# contactless-thermometer.net
KiCad netlist of a schematic drawn in EAGLE
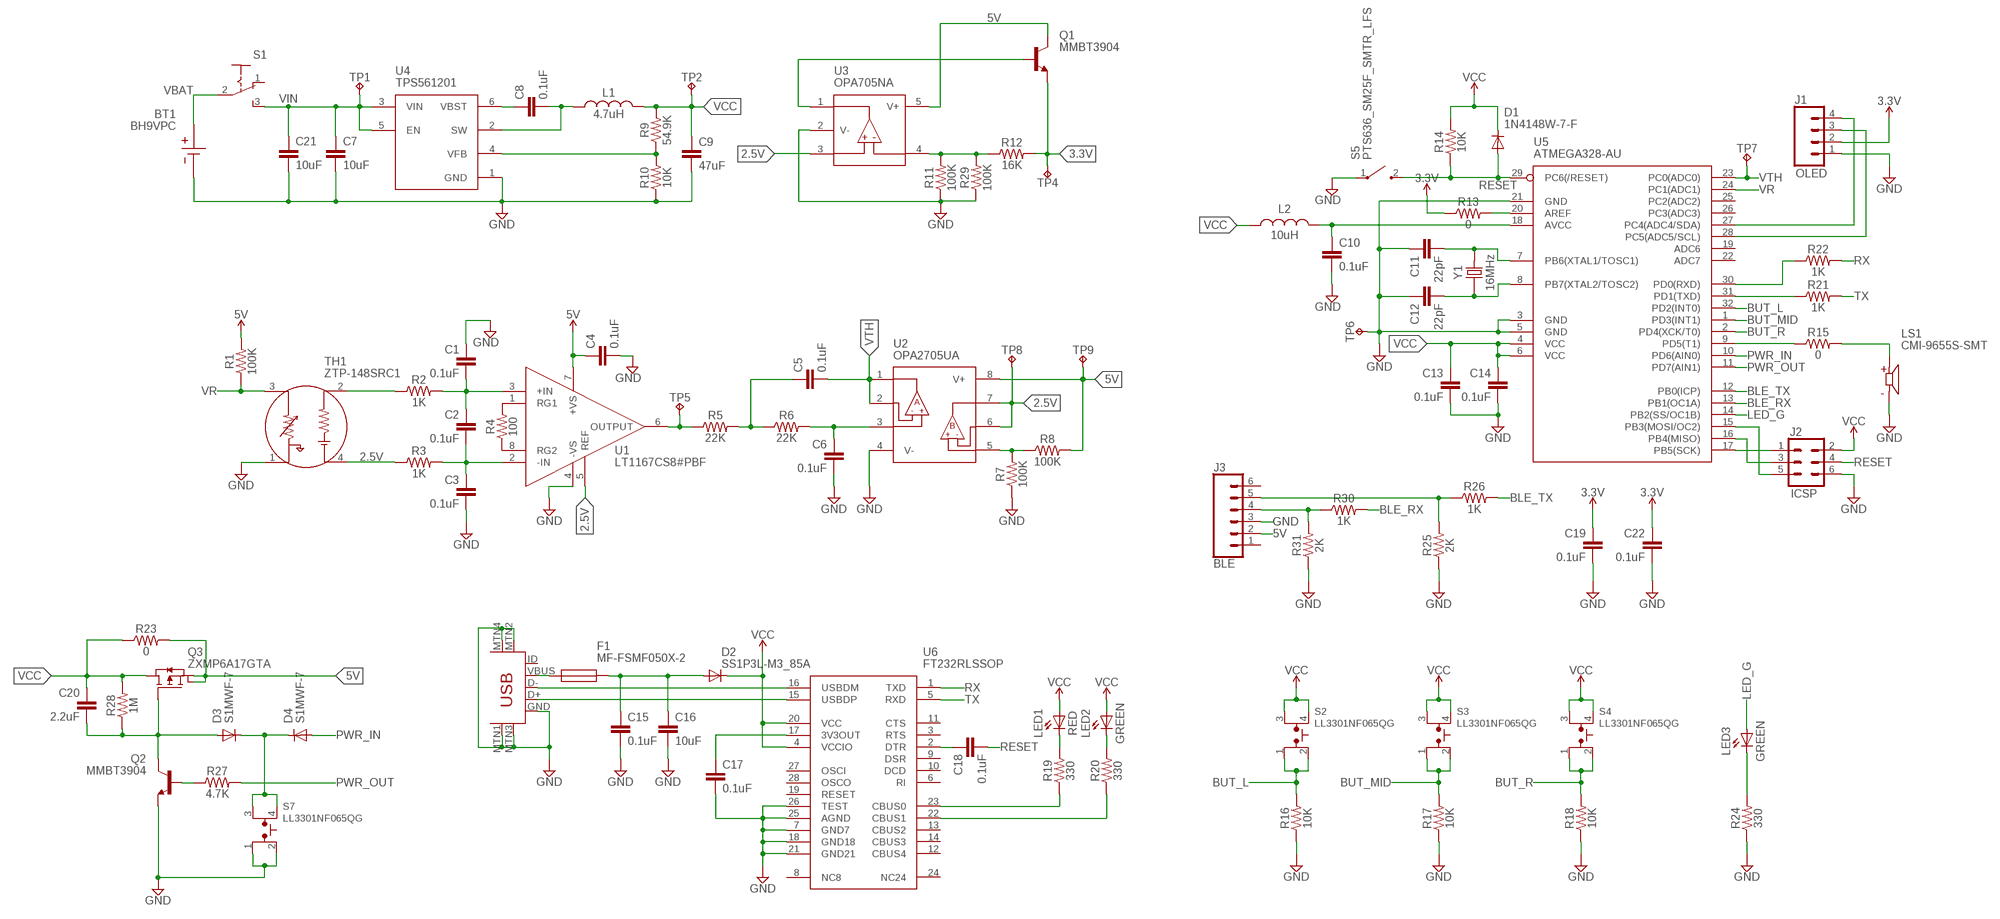
[diagram p0: schematic, sheet 1]

(export (version "E")
  (design (tool "Eeschema 10.0.6"))
  (components
    (comp (ref "BT1")
      (value "BH9VPC")
      (footprint "eagle-import:BAT_BH9VPC")
      (fields (field (name "DIGI-KEY_PART_NUMBER") "BH9V-PC-ND") (field (name "MF") "MPD"))
      (libsource (lib "eagle-import") (part "BH9VPC"))
    )
    (comp (ref "C1")
      (value "0.1uF")
      (footprint "eagle-import:0603")
      (libsource (lib "eagle-import") (part "0.1UF-0603-25V-(+80/-20%)"))
    )
    (comp (ref "C2")
      (value "0.1uF")
      (footprint "eagle-import:0603")
      (libsource (lib "eagle-import") (part "0.1UF-0603-25V-(+80/-20%)"))
    )
    (comp (ref "C3")
      (value "0.1uF")
      (footprint "eagle-import:0603")
      (libsource (lib "eagle-import") (part "0.1UF-0603-25V-(+80/-20%)"))
    )
    (comp (ref "C4")
      (value "0.1uF")
      (footprint "eagle-import:0603")
      (libsource (lib "eagle-import") (part "0.1UF-0603-25V-(+80/-20%)"))
    )
    (comp (ref "C5")
      (value "0.1uF")
      (footprint "eagle-import:0603")
      (libsource (lib "eagle-import") (part "0.1UF-0603-25V-(+80/-20%)"))
    )
    (comp (ref "C6")
      (value "0.1uF")
      (footprint "eagle-import:0603")
      (libsource (lib "eagle-import") (part "0.1UF-0603-25V-(+80/-20%)"))
    )
    (comp (ref "C7")
      (value "10uF")
      (footprint "eagle-import:CAPC2012X145N")
      (fields (field (name "MF") "Murata") (field (name "MP") "GRM21BR6YA106KE43L"))
      (libsource (lib "eagle-import") (part "GRM21BR6YA106KE43L"))
    )
    (comp (ref "C8")
      (value "0.1uF")
      (footprint "eagle-import:0603")
      (libsource (lib "eagle-import") (part "0.1UF-0603-25V-(+80/-20%)"))
    )
    (comp (ref "C9")
      (value "47uF")
      (footprint "eagle-import:1206")
      (libsource (lib "eagle-import") (part "10UF-1206-6.3V-20%"))
    )
    (comp (ref "C10")
      (value "0.1uF")
      (footprint "eagle-import:0603")
      (libsource (lib "eagle-import") (part "0.1UF-0603-25V-(+80/-20%)"))
    )
    (comp (ref "C11")
      (value "22pF")
      (footprint "eagle-import:0603")
      (libsource (lib "eagle-import") (part "0.1UF-0603-25V-(+80/-20%)"))
    )
    (comp (ref "C12")
      (value "22pF")
      (footprint "eagle-import:0603")
      (libsource (lib "eagle-import") (part "0.1UF-0603-25V-(+80/-20%)"))
    )
    (comp (ref "C13")
      (value "0.1uF")
      (footprint "eagle-import:0603")
      (libsource (lib "eagle-import") (part "0.1UF-0603-25V-(+80/-20%)"))
    )
    (comp (ref "C14")
      (value "0.1uF")
      (footprint "eagle-import:0603")
      (libsource (lib "eagle-import") (part "0.1UF-0603-25V-(+80/-20%)"))
    )
    (comp (ref "C15")
      (value "0.1uF")
      (footprint "eagle-import:0603")
      (libsource (lib "eagle-import") (part "0.1UF-0603-25V-(+80/-20%)"))
    )
    (comp (ref "C16")
      (value "10uF")
      (footprint "eagle-import:1206")
      (libsource (lib "eagle-import") (part "10UF-1206-6.3V-20%"))
    )
    (comp (ref "C17")
      (value "0.1uF")
      (footprint "eagle-import:0603")
      (libsource (lib "eagle-import") (part "0.1UF-0603-25V-(+80/-20%)"))
    )
    (comp (ref "C18")
      (value "0.1uF")
      (footprint "eagle-import:0603")
      (libsource (lib "eagle-import") (part "0.1UF-0603-25V-(+80/-20%)"))
    )
    (comp (ref "C19")
      (value "0.1uF")
      (footprint "eagle-import:0603")
      (libsource (lib "eagle-import") (part "0.1UF-0603-25V-(+80/-20%)"))
    )
    (comp (ref "C20")
      (value "2.2uF")
      (footprint "eagle-import:CAPC2012X145N")
      (fields (field (name "MF") "Murata") (field (name "MP") "GRM21BR6YA106KE43L"))
      (libsource (lib "eagle-import") (part "GRM21BR6YA106KE43L"))
    )
    (comp (ref "C21")
      (value "10uF")
      (footprint "eagle-import:CAPC2012X145N")
      (fields (field (name "MF") "Murata") (field (name "MP") "GRM21BR6YA106KE43L"))
      (libsource (lib "eagle-import") (part "GRM21BR6YA106KE43L"))
    )
    (comp (ref "C22")
      (value "0.1uF")
      (footprint "eagle-import:0603")
      (libsource (lib "eagle-import") (part "0.1UF-0603-25V-(+80/-20%)"))
    )
    (comp (ref "D1")
      (value "1N4148W-7-F")
      (footprint "eagle-import:SOD3716X145N")
      (fields (field (name "MOUSER_PART_NUMBER") "621-1N4148W-F"))
      (libsource (lib "eagle-import") (part "1N4148W-7-F"))
    )
    (comp (ref "D2")
      (value "SS1P3L-M3_85A")
      (footprint "eagle-import:SMP")
      (fields
        (field (name "MANUFACTURER_PART_NUMBER") "SS1P3L-M3/85A")
        (field (name "MOUSER_PART_NUMBER") "625-SS1P3L-M3/85A")
      )
      (libsource (lib "eagle-import") (part "SS1P3L-M3_85A"))
    )
    (comp (ref "D3")
      (value "S1MWF-7")
      (footprint "eagle-import:SODFL3518X115N")
      (fields (field (name "MOUSER_PART_NUMBER") "621-S1MWF-7"))
      (libsource (lib "eagle-import") (part "S1MWF-7"))
    )
    (comp (ref "D4")
      (value "S1MWF-7")
      (footprint "eagle-import:SODFL3518X115N")
      (fields (field (name "MOUSER_PART_NUMBER") "621-S1MWF-7"))
      (libsource (lib "eagle-import") (part "S1MWF-7"))
    )
    (comp (ref "F1")
      (value "MF-FSMF050X-2")
      (footprint "eagle-import:FUSC1608X100N")
      (fields (field (name "MOUSER_PART_NUMBER") "652-MFFSMF050X-2"))
      (libsource (lib "eagle-import") (part "MF-FSMF050X-2"))
    )
    (comp (ref "J1")
      (value "OLED")
      (footprint "eagle-import:1X04")
      (libsource (lib "eagle-import") (part "CONN_04"))
    )
    (comp (ref "J2")
      (value "ICSP")
      (footprint "eagle-import:2X3")
      (libsource (lib "eagle-import") (part "CONN_03X22X3_SILK_MALE_PTH"))
    )
    (comp (ref "J3")
      (value "BLE")
      (footprint "eagle-import:1X06")
      (libsource (lib "eagle-import") (part "CONN_06SILK_FEMALE_PTH"))
    )
    (comp (ref "J4")
      (value "USB-MINIB-5PIN")
      (footprint "eagle-import:USB-MINIB")
      (libsource (lib "eagle-import") (part "USB-MINIB-5PIN"))
    )
    (comp (ref "L1")
      (value "4.7uH")
      (footprint "eagle-import:VLCF5020T4R7N1R71")
      (fields
        (field (name "MANUFACTURER_PART_NUMBER") "VLCF5020T-4R7N1R7-1")
        (field (name "MOUSER_PART_NUMBER") "810-VLCF52T4R7N1R71")
      )
      (libsource (lib "eagle-import") (part "VLCF5020T-4R7N1R7-1"))
    )
    (comp (ref "L2")
      (value "10uH")
      (footprint "eagle-import:INDC2012X145N")
      (fields
        (field (name "DIGI-KEY_PART_NUMBER") "587-2530-1-ND")
        (field (name "MF") "Taiyo Yuden")
        (field (name "MP") "LBC2012T100K")
      )
      (libsource (lib "eagle-import") (part "LBC2012T100K"))
    )
    (comp (ref "LED1")
      (value "RED")
      (footprint "eagle-import:AA1608CGSK")
      (fields
        (field (name "MANUFACTURER_PART_NUMBER") "AA1608CGSK")
        (field (name "MOUSER_PART_NUMBER") "604-AA1608CGSK")
      )
      (libsource (lib "eagle-import") (part "AA1608CGSK"))
    )
    (comp (ref "LED2")
      (value "GREEN")
      (footprint "eagle-import:AA1608CGSK")
      (fields
        (field (name "MANUFACTURER_PART_NUMBER") "AA1608CGSK")
        (field (name "MOUSER_PART_NUMBER") "604-AA1608CGSK")
      )
      (libsource (lib "eagle-import") (part "AA1608CGSK"))
    )
    (comp (ref "LED3")
      (value "GREEN")
      (footprint "eagle-import:AA1608CGSK")
      (fields
        (field (name "MANUFACTURER_PART_NUMBER") "AA1608CGSK")
        (field (name "MOUSER_PART_NUMBER") "604-AA1608CGSK")
      )
      (libsource (lib "eagle-import") (part "AA1608CGSK"))
    )
    (comp (ref "LS1")
      (value "CMI-9655S-SMT")
      (footprint "eagle-import:CUI_CMI-9655S-SMT")
      (fields (field (name "MF") "CUI Devices") (field (name "MP") "CMI-9655S-SMT-TR"))
      (libsource (lib "eagle-import") (part "CMI-9655S-SMT"))
    )
    (comp (ref "Q1")
      (value "MMBT3904")
      (footprint "eagle-import:SOT23_NXP")
      (libsource (lib "eagle-import") (part "MMBT3904"))
    )
    (comp (ref "Q2")
      (value "MMBT3904")
      (footprint "eagle-import:SOT23_NXP")
      (libsource (lib "eagle-import") (part "MMBT3904"))
    )
    (comp (ref "Q3")
      (value "ZXMP6A17GTA")
      (footprint "eagle-import:SOT230P700X180-4N")
      (fields (field (name "MOUSER_PART_NUMBER") "522-ZXMP6A17GTA"))
      (libsource (lib "eagle-import") (part "ZXMP6A17GTA"))
    )
    (comp (ref "R1")
      (value "100K")
      (footprint "eagle-import:0603")
      (libsource (lib "eagle-import") (part "RESISTOR0603"))
    )
    (comp (ref "R2")
      (value "1K")
      (footprint "eagle-import:0603")
      (libsource (lib "eagle-import") (part "RESISTOR0603"))
    )
    (comp (ref "R3")
      (value "1K")
      (footprint "eagle-import:0603")
      (libsource (lib "eagle-import") (part "RESISTOR0603"))
    )
    (comp (ref "R4")
      (value "100")
      (footprint "eagle-import:0603")
      (libsource (lib "eagle-import") (part "RESISTOR0603"))
    )
    (comp (ref "R5")
      (value "22K")
      (footprint "eagle-import:0603")
      (libsource (lib "eagle-import") (part "RESISTOR0603"))
    )
    (comp (ref "R6")
      (value "22K")
      (footprint "eagle-import:0603")
      (libsource (lib "eagle-import") (part "RESISTOR0603"))
    )
    (comp (ref "R7")
      (value "100K")
      (footprint "eagle-import:0603")
      (libsource (lib "eagle-import") (part "RESISTOR0603"))
    )
    (comp (ref "R8")
      (value "100K")
      (footprint "eagle-import:0603")
      (libsource (lib "eagle-import") (part "RESISTOR0603"))
    )
    (comp (ref "R9")
      (value "54.9K")
      (footprint "eagle-import:0603")
      (libsource (lib "eagle-import") (part "RESISTOR0603"))
    )
    (comp (ref "R10")
      (value "10K")
      (footprint "eagle-import:0603")
      (libsource (lib "eagle-import") (part "RESISTOR0603"))
    )
    (comp (ref "R11")
      (value "100K")
      (footprint "eagle-import:0603")
      (libsource (lib "eagle-import") (part "RESISTOR0603"))
    )
    (comp (ref "R12")
      (value "16K")
      (footprint "eagle-import:0603")
      (libsource (lib "eagle-import") (part "RESISTOR0603"))
    )
    (comp (ref "R13")
      (value "0")
      (footprint "eagle-import:0603")
      (libsource (lib "eagle-import") (part "RESISTOR0603"))
    )
    (comp (ref "R14")
      (value "10K")
      (footprint "eagle-import:0603")
      (libsource (lib "eagle-import") (part "RESISTOR0603"))
    )
    (comp (ref "R15")
      (value "0")
      (footprint "eagle-import:0603")
      (libsource (lib "eagle-import") (part "RESISTOR0603"))
    )
    (comp (ref "R16")
      (value "10K")
      (footprint "eagle-import:0603")
      (libsource (lib "eagle-import") (part "RESISTOR0603"))
    )
    (comp (ref "R17")
      (value "10K")
      (footprint "eagle-import:0603")
      (libsource (lib "eagle-import") (part "RESISTOR0603"))
    )
    (comp (ref "R18")
      (value "10K")
      (footprint "eagle-import:0603")
      (libsource (lib "eagle-import") (part "RESISTOR0603"))
    )
    (comp (ref "R19")
      (value "330")
      (footprint "eagle-import:0603")
      (libsource (lib "eagle-import") (part "RESISTOR0603"))
    )
    (comp (ref "R20")
      (value "330")
      (footprint "eagle-import:0603")
      (libsource (lib "eagle-import") (part "RESISTOR0603"))
    )
    (comp (ref "R21")
      (value "1K")
      (footprint "eagle-import:0603")
      (libsource (lib "eagle-import") (part "RESISTOR0603"))
    )
    (comp (ref "R22")
      (value "1K")
      (footprint "eagle-import:0603")
      (libsource (lib "eagle-import") (part "RESISTOR0603"))
    )
    (comp (ref "R23")
      (value "0")
      (footprint "eagle-import:0603")
      (libsource (lib "eagle-import") (part "RESISTOR0603"))
    )
    (comp (ref "R24")
      (value "330")
      (footprint "eagle-import:0603")
      (libsource (lib "eagle-import") (part "RESISTOR0603"))
    )
    (comp (ref "R25")
      (value "2K")
      (footprint "eagle-import:0603")
      (libsource (lib "eagle-import") (part "RESISTOR0603"))
    )
    (comp (ref "R26")
      (value "1K")
      (footprint "eagle-import:0603")
      (libsource (lib "eagle-import") (part "RESISTOR0603"))
    )
    (comp (ref "R27")
      (value "4.7K")
      (footprint "eagle-import:0603")
      (libsource (lib "eagle-import") (part "RESISTOR0603"))
    )
    (comp (ref "R28")
      (value "1M")
      (footprint "eagle-import:0603")
      (libsource (lib "eagle-import") (part "RESISTOR0603"))
    )
    (comp (ref "R29")
      (value "100K")
      (footprint "eagle-import:0603")
      (libsource (lib "eagle-import") (part "RESISTOR0603"))
    )
    (comp (ref "R30")
      (value "1K")
      (footprint "eagle-import:0603")
      (libsource (lib "eagle-import") (part "RESISTOR0603"))
    )
    (comp (ref "R31")
      (value "2K")
      (footprint "eagle-import:0603")
      (libsource (lib "eagle-import") (part "RESISTOR0603"))
    )
    (comp (ref "S1")
      (value "SK12F17G7")
      (footprint "eagle-import:SW3_2F17G7_CNK")
      (fields (field (name "COPYRIGHT") "Copyright (C) 2018 Accelerated Designs. All rights reserved"))
      (libsource (lib "eagle-import") (part "SK12F17G7"))
    )
    (comp (ref "S2")
      (value "LL3301NF065QG")
      (footprint "eagle-import:LL3301NF065QG")
      (fields (field (name "MOUSER_PART_NUMBER") "612-LL3301NF065QG"))
      (libsource (lib "eagle-import") (part "LL3301NF065QG"))
    )
    (comp (ref "S3")
      (value "LL3301NF065QG")
      (footprint "eagle-import:LL3301NF065QG")
      (fields (field (name "MOUSER_PART_NUMBER") "612-LL3301NF065QG"))
      (libsource (lib "eagle-import") (part "LL3301NF065QG"))
    )
    (comp (ref "S4")
      (value "LL3301NF065QG")
      (footprint "eagle-import:LL3301NF065QG")
      (fields (field (name "MOUSER_PART_NUMBER") "612-LL3301NF065QG"))
      (libsource (lib "eagle-import") (part "LL3301NF065QG"))
    )
    (comp (ref "S5")
      (value "PTS636_SM25F_SMTR_LFS")
      (footprint "eagle-import:PTS636SM25FSMTRLFS")
      (fields
        (field (name "MANUFACTURER_PART_NUMBER") "PTS636 SM25F SMTR LFS")
        (field (name "MOUSER_PART_NUMBER") "611-PTS636SM25FSMTRL")
      )
      (libsource (lib "eagle-import") (part "PTS636_SM25F_SMTR_LFS"))
    )
    (comp (ref "S7")
      (value "LL3301NF065QG")
      (footprint "eagle-import:LL3301NF065QG")
      (fields (field (name "MOUSER_PART_NUMBER") "612-LL3301NF065QG"))
      (libsource (lib "eagle-import") (part "LL3301NF065QG"))
    )
    (comp (ref "TH1")
      (value "ZTP-148SRC1")
      (footprint "eagle-import:XDCR_ZTP-148SRC1")
      (fields
        (field (name "DIGI-KEY_PART_NUMBER") "45-ZTP-148SRC1-ND")
        (field (name "MF") "Amphenol Advanced Sensors")
      )
      (libsource (lib "eagle-import") (part "ZTP-148SRC1"))
    )
    (comp (ref "TP1")
      (value "TPTP10R")
      (footprint "eagle-import:TP10R")
      (libsource (lib "eagle-import") (part "TPTP10R"))
    )
    (comp (ref "TP2")
      (value "TPTP10R")
      (footprint "eagle-import:TP10R")
      (libsource (lib "eagle-import") (part "TPTP10R"))
    )
    (comp (ref "TP4")
      (value "TPTP10R")
      (footprint "eagle-import:TP10R")
      (libsource (lib "eagle-import") (part "TPTP10R"))
    )
    (comp (ref "TP5")
      (value "TPTP10R")
      (footprint "eagle-import:TP10R")
      (libsource (lib "eagle-import") (part "TPTP10R"))
    )
    (comp (ref "TP6")
      (value "TPTP10R")
      (footprint "eagle-import:TP10R")
      (libsource (lib "eagle-import") (part "TPTP10R"))
    )
    (comp (ref "TP7")
      (value "TPTP10R")
      (footprint "eagle-import:TP10R")
      (libsource (lib "eagle-import") (part "TPTP10R"))
    )
    (comp (ref "TP8")
      (value "TPTP10R")
      (footprint "eagle-import:TP10R")
      (libsource (lib "eagle-import") (part "TPTP10R"))
    )
    (comp (ref "TP9")
      (value "TPTP10R")
      (footprint "eagle-import:TP10R")
      (libsource (lib "eagle-import") (part "TPTP10R"))
    )
    (comp (ref "U1")
      (value "LT1167CS8#PBF")
      (footprint "eagle-import:SOIC127P599X175-8N")
      (fields (field (name "MOUSER_PART_NUMBER") "584-LT1167CS8#PBF"))
      (libsource (lib "eagle-import") (part "LT1167CS8#PBF"))
    )
    (comp (ref "U2")
      (value "OPA2705UA")
      (footprint "eagle-import:SOIC127P600X175-8N")
      (fields (field (name "MOUSER_PART_NUMBER") "595-OPA2705UA"))
      (libsource (lib "eagle-import") (part "OPA2705UA"))
    )
    (comp (ref "U3")
      (value "OPA705NA")
      (footprint "eagle-import:SOT95P280X145-5N")
      (fields
        (field (name "MANUFACTURER_PART_NUMBER") "OPA705NA/3K")
        (field (name "MOUSER_PART_NUMBER") "595-OPA705NA/3K")
      )
      (libsource (lib "eagle-import") (part "OPA705NA_3K"))
    )
    (comp (ref "U4")
      (value "TPS561201")
      (footprint "eagle-import:SOT95P280X110-6N")
      (fields
        (field (name "MANUFACTURER_PART_NUMBER") "TPS561201DDCR")
        (field (name "MOUSER_PART_NUMBER") "595-TPS561201DDCR")
      )
      (libsource (lib "eagle-import") (part "TPS561201DDCR"))
    )
    (comp (ref "U5")
      (value "ATMEGA328-AU")
      (footprint "eagle-import:TQFP32-08")
      (fields (field (name "MPN") "ATMEGA8-16AU"))
      (libsource (lib "eagle-import") (part "MEGA8-AI"))
    )
    (comp (ref "U6")
      (value "FT232RLSSOP")
      (footprint "eagle-import:SOP65P780X200-28N")
      (fields
        (field (name "MANUFACTURER_PART_NUMBER") "FT232RL-TUBE")
        (field (name "MOUSER_PART_NUMBER") "895-FT232RL-TUBE")
      )
      (libsource (lib "eagle-import") (part "FT232RLSSOP"))
    )
    (comp (ref "Y1")
      (value "16MHz")
      (footprint "eagle-import:XTAL_ECS-240-20-5PX-TR")
      (fields
        (field (name "DIGI-KEY_PART_NUMBER") "XC1255CT-ND")
        (field (name "MF") "ECS Inc.")
        (field (name "MP") "ECS-240-20-5PX-TR")
      )
      (libsource (lib "eagle-import") (part "ECS-240-20-5PX-TR"))
    )
  )
  (nets
    (net (code "1") (name "/BLE_RX") (class "Default")
      (node (ref "R30") (pin "2") (pinfunction "2_2") (pintype "passive"))
      (node (ref "U5") (pin "13") (pinfunction "PB1(OC1A)_13") (pintype "bidirectional"))
    )
    (net (code "2") (name "/BLE_TX") (class "Default")
      (node (ref "R26") (pin "2") (pinfunction "2_2") (pintype "passive"))
      (node (ref "U5") (pin "12") (pinfunction "PB0(ICP)_12") (pintype "bidirectional"))
    )
    (net (code "3") (name "/BUT_L") (class "Default")
      (node (ref "R16") (pin "2") (pinfunction "2_2") (pintype "passive"))
      (node (ref "S2") (pin "1") (pinfunction "1_1") (pintype "bidirectional"))
      (node (ref "S2") (pin "2") (pinfunction "2_2") (pintype "bidirectional"))
      (node (ref "U5") (pin "32") (pinfunction "PD2(INT0)_32") (pintype "bidirectional"))
    )
    (net (code "4") (name "/BUT_MID") (class "Default")
      (node (ref "R17") (pin "2") (pinfunction "2_2") (pintype "passive"))
      (node (ref "S3") (pin "1") (pinfunction "1_1") (pintype "bidirectional"))
      (node (ref "S3") (pin "2") (pinfunction "2_2") (pintype "bidirectional"))
      (node (ref "U5") (pin "1") (pinfunction "PD3(INT1)_1") (pintype "bidirectional"))
    )
    (net (code "5") (name "/BUT_R") (class "Default")
      (node (ref "R18") (pin "2") (pinfunction "2_2") (pintype "passive"))
      (node (ref "S4") (pin "1") (pinfunction "1_1") (pintype "bidirectional"))
      (node (ref "S4") (pin "2") (pinfunction "2_2") (pintype "bidirectional"))
      (node (ref "U5") (pin "2") (pinfunction "PD4(XCK/T0)_2") (pintype "bidirectional"))
    )
    (net (code "6") (name "/LED_G") (class "Default")
      (node (ref "LED3") (pin "2") (pinfunction "A_2") (pintype "bidirectional"))
      (node (ref "U5") (pin "14") (pinfunction "PB2(SS/OC1B)_14") (pintype "bidirectional"))
    )
    (net (code "7") (name "/PWR_IN") (class "Default")
      (node (ref "D4") (pin "2") (pinfunction "A_2") (pintype "bidirectional"))
      (node (ref "U5") (pin "10") (pinfunction "PD6(AIN0)_10") (pintype "bidirectional"))
    )
    (net (code "8") (name "/PWR_OUT") (class "Default")
      (node (ref "R27") (pin "2") (pinfunction "2_2") (pintype "passive"))
      (node (ref "U5") (pin "11") (pinfunction "PD7(AIN1)_11") (pintype "bidirectional"))
    )
    (net (code "9") (name "/RESET") (class "Default")
      (node (ref "C18") (pin "2") (pinfunction "2_2") (pintype "passive"))
      (node (ref "D1") (pin "2") (pinfunction "A_2") (pintype "bidirectional"))
      (node (ref "J2") (pin "4") (pinfunction "4_4") (pintype "bidirectional"))
      (node (ref "R14") (pin "1") (pinfunction "1_1") (pintype "passive"))
      (node (ref "S5") (pin "2") (pinfunction "NO_2") (pintype "bidirectional"))
      (node (ref "U5") (pin "29") (pinfunction "PC6(/RESET)_29") (pintype "bidirectional"))
    )
    (net (code "10") (name "/RX") (class "Default")
      (node (ref "R22") (pin "2") (pinfunction "2_2") (pintype "passive"))
      (node (ref "U6") (pin "1") (pinfunction "TXD_1") (pintype "bidirectional"))
    )
    (net (code "11") (name "/TX") (class "Default")
      (node (ref "R21") (pin "2") (pinfunction "2_2") (pintype "passive"))
      (node (ref "U6") (pin "5") (pinfunction "RXD_5") (pintype "bidirectional"))
    )
    (net (code "12") (name "/VBAT") (class "Default")
      (node (ref "BT1") (pin "+") (pinfunction "+_+") (pintype "passive"))
      (node (ref "S1") (pin "2") (pinfunction "2_2") (pintype "passive"))
    )
    (net (code "13") (name "/VIN") (class "Default")
      (node (ref "C21") (pin "2") (pinfunction "2_2") (pintype "passive"))
      (node (ref "C7") (pin "2") (pinfunction "2_2") (pintype "passive"))
      (node (ref "S1") (pin "3") (pinfunction "3_3") (pintype "passive"))
      (node (ref "TP1") (pin "TP") (pinfunction "TP_TP") (pintype "input"))
      (node (ref "U4") (pin "3") (pinfunction "VIN_3") (pintype "bidirectional"))
      (node (ref "U4") (pin "5") (pinfunction "EN_5") (pintype "bidirectional"))
    )
    (net (code "14") (name "/VR") (class "Default")
      (node (ref "R1") (pin "1") (pinfunction "1_1") (pintype "passive"))
      (node (ref "TH1") (pin "3") (pinfunction "THERMISTOR_3") (pintype "passive"))
      (node (ref "U5") (pin "24") (pinfunction "PC1(ADC1)_24") (pintype "bidirectional"))
    )
    (net (code "15") (name "2.5V") (class "Default")
      (node (ref "R3") (pin "1") (pinfunction "1_1") (pintype "passive"))
      (node (ref "TH1") (pin "4") (pinfunction "THERMOPILE_GND_4") (pintype "power_in"))
      (node (ref "TP8") (pin "TP") (pinfunction "TP_TP") (pintype "input"))
      (node (ref "U1") (pin "5") (pinfunction "REF_5") (pintype "power_in"))
      (node (ref "U2") (pin "6") (pinfunction "-INB_6") (pintype "bidirectional"))
      (node (ref "U2") (pin "7") (pinfunction "OUTB_7") (pintype "bidirectional"))
      (node (ref "U3") (pin "3") (pinfunction "+IN_3") (pintype "bidirectional"))
    )
    (net (code "16") (name "3.3V") (class "Default")
      (node (ref "C19") (pin "1") (pinfunction "1_1") (pintype "passive"))
      (node (ref "C22") (pin "1") (pinfunction "1_1") (pintype "passive"))
      (node (ref "J1") (pin "2") (pinfunction "2_2") (pintype "passive"))
      (node (ref "Q1") (pin "2") (pinfunction "2_2") (pintype "passive"))
      (node (ref "R12") (pin "2") (pinfunction "2_2") (pintype "passive"))
      (node (ref "R13") (pin "1") (pinfunction "1_1") (pintype "passive"))
      (node (ref "TP4") (pin "TP") (pinfunction "TP_TP") (pintype "input"))
    )
    (net (code "17") (name "5V") (class "Default")
      (node (ref "C4") (pin "1") (pinfunction "1_1") (pintype "passive"))
      (node (ref "J3") (pin "2") (pinfunction "2_2") (pintype "passive"))
      (node (ref "Q1") (pin "3") (pinfunction "3_3") (pintype "passive"))
      (node (ref "Q3") (pin "2") (pinfunction "D1_2") (pintype "bidirectional"))
      (node (ref "Q3") (pin "4") (pinfunction "D2_4") (pintype "bidirectional"))
      (node (ref "R1") (pin "2") (pinfunction "2_2") (pintype "passive"))
      (node (ref "R23") (pin "2") (pinfunction "2_2") (pintype "passive"))
      (node (ref "R8") (pin "2") (pinfunction "2_2") (pintype "passive"))
      (node (ref "TP9") (pin "TP") (pinfunction "TP_TP") (pintype "input"))
      (node (ref "U1") (pin "7") (pinfunction "+VS_7") (pintype "power_in"))
      (node (ref "U2") (pin "8") (pinfunction "V+_8") (pintype "power_in"))
      (node (ref "U3") (pin "5") (pinfunction "V+_5") (pintype "bidirectional"))
    )
    (net (code "18") (name "GND") (class "Default")
      (node (ref "BT1") (pin "-") (pinfunction "-_-") (pintype "passive"))
      (node (ref "C1") (pin "1") (pinfunction "1_1") (pintype "passive"))
      (node (ref "C10") (pin "2") (pinfunction "2_2") (pintype "passive"))
      (node (ref "C11") (pin "1") (pinfunction "1_1") (pintype "passive"))
      (node (ref "C12") (pin "1") (pinfunction "1_1") (pintype "passive"))
      (node (ref "C13") (pin "2") (pinfunction "2_2") (pintype "passive"))
      (node (ref "C14") (pin "2") (pinfunction "2_2") (pintype "passive"))
      (node (ref "C15") (pin "2") (pinfunction "2_2") (pintype "passive"))
      (node (ref "C16") (pin "2") (pinfunction "2_2") (pintype "passive"))
      (node (ref "C17") (pin "2") (pinfunction "2_2") (pintype "passive"))
      (node (ref "C19") (pin "2") (pinfunction "2_2") (pintype "passive"))
      (node (ref "C21") (pin "1") (pinfunction "1_1") (pintype "passive"))
      (node (ref "C22") (pin "2") (pinfunction "2_2") (pintype "passive"))
      (node (ref "C3") (pin "2") (pinfunction "2_2") (pintype "passive"))
      (node (ref "C4") (pin "2") (pinfunction "2_2") (pintype "passive"))
      (node (ref "C6") (pin "2") (pinfunction "2_2") (pintype "passive"))
      (node (ref "C7") (pin "1") (pinfunction "1_1") (pintype "passive"))
      (node (ref "C9") (pin "2") (pinfunction "2_2") (pintype "passive"))
      (node (ref "J1") (pin "1") (pinfunction "1_1") (pintype "passive"))
      (node (ref "J2") (pin "6") (pinfunction "6_6") (pintype "bidirectional"))
      (node (ref "J3") (pin "3") (pinfunction "3_3") (pintype "passive"))
      (node (ref "J4") (pin "GND") (pinfunction "GND_GND") (pintype "bidirectional"))
      (node (ref "J4") (pin "MTN1") (pinfunction "MTN2_MTN1") (pintype "bidirectional"))
      (node (ref "J4") (pin "MTN2") (pinfunction "MTN3_MTN2") (pintype "bidirectional"))
      (node (ref "J4") (pin "MTN3") (pinfunction "MTN1_MTN3") (pintype "bidirectional"))
      (node (ref "J4") (pin "MTN4") (pinfunction "MTN4_MTN4") (pintype "bidirectional"))
      (node (ref "LS1") (pin "N") (pinfunction "N_N") (pintype "passive"))
      (node (ref "Q2") (pin "2") (pinfunction "2_2") (pintype "passive"))
      (node (ref "R10") (pin "1") (pinfunction "1_1") (pintype "passive"))
      (node (ref "R11") (pin "1") (pinfunction "1_1") (pintype "passive"))
      (node (ref "R16") (pin "1") (pinfunction "1_1") (pintype "passive"))
      (node (ref "R17") (pin "1") (pinfunction "1_1") (pintype "passive"))
      (node (ref "R18") (pin "1") (pinfunction "1_1") (pintype "passive"))
      (node (ref "R24") (pin "1") (pinfunction "1_1") (pintype "passive"))
      (node (ref "R25") (pin "1") (pinfunction "1_1") (pintype "passive"))
      (node (ref "R29") (pin "1") (pinfunction "1_1") (pintype "passive"))
      (node (ref "R31") (pin "1") (pinfunction "1_1") (pintype "passive"))
      (node (ref "R7") (pin "1") (pinfunction "1_1") (pintype "passive"))
      (node (ref "S5") (pin "1") (pinfunction "COM_1") (pintype "bidirectional"))
      (node (ref "S7") (pin "1") (pinfunction "1_1") (pintype "bidirectional"))
      (node (ref "S7") (pin "2") (pinfunction "2_2") (pintype "bidirectional"))
      (node (ref "TH1") (pin "1") (pinfunction "THERMISTOR_GND_1") (pintype "power_in"))
      (node (ref "TP6") (pin "TP") (pinfunction "TP_TP") (pintype "input"))
      (node (ref "U1") (pin "4") (pinfunction "-VS_4") (pintype "power_in"))
      (node (ref "U2") (pin "4") (pinfunction "V-_4") (pintype "power_in"))
      (node (ref "U3") (pin "2") (pinfunction "V-_2") (pintype "bidirectional"))
      (node (ref "U4") (pin "1") (pinfunction "GND_1") (pintype "bidirectional"))
      (node (ref "U5") (pin "21") (pinfunction "GND_21") (pintype "power_in"))
      (node (ref "U5") (pin "3") (pinfunction "GND_3") (pintype "power_in"))
      (node (ref "U5") (pin "5") (pinfunction "GND_5") (pintype "power_in"))
      (node (ref "U6") (pin "18") (pinfunction "GND18_18") (pintype "bidirectional"))
      (node (ref "U6") (pin "21") (pinfunction "GND21_21") (pintype "bidirectional"))
      (node (ref "U6") (pin "25") (pinfunction "AGND_25") (pintype "bidirectional"))
      (node (ref "U6") (pin "26") (pinfunction "TEST_26") (pintype "bidirectional"))
      (node (ref "U6") (pin "7") (pinfunction "GND7_7") (pintype "bidirectional"))
    )
    (net (code "19") (name "Net-(C5-Pad1)") (class "Default")
      (node (ref "C5") (pin "1") (pinfunction "1_1") (pintype "passive"))
      (node (ref "R5") (pin "2") (pinfunction "2_2") (pintype "passive"))
      (node (ref "R6") (pin "1") (pinfunction "1_1") (pintype "passive"))
    )
    (net (code "20") (name "Net-(D2-A)") (class "Default")
      (node (ref "C15") (pin "1") (pinfunction "1_1") (pintype "passive"))
      (node (ref "C16") (pin "1") (pinfunction "1_1") (pintype "passive"))
      (node (ref "D2") (pin "1") (pinfunction "A_1") (pintype "bidirectional"))
      (node (ref "F1") (pin "2") (pinfunction "2_2") (pintype "bidirectional"))
    )
    (net (code "21") (name "Net-(D3-A)") (class "Default")
      (node (ref "C20") (pin "1") (pinfunction "1_1") (pintype "passive"))
      (node (ref "D3") (pin "2") (pinfunction "A_2") (pintype "bidirectional"))
      (node (ref "Q2") (pin "3") (pinfunction "3_3") (pintype "passive"))
      (node (ref "Q3") (pin "1") (pinfunction "G_1") (pintype "bidirectional"))
      (node (ref "R28") (pin "1") (pinfunction "1_1") (pintype "passive"))
    )
    (net (code "22") (name "Net-(D3-K)") (class "Default")
      (node (ref "D3") (pin "1") (pinfunction "K_1") (pintype "bidirectional"))
      (node (ref "D4") (pin "1") (pinfunction "K_1") (pintype "bidirectional"))
      (node (ref "S7") (pin "3") (pinfunction "3_3") (pintype "bidirectional"))
      (node (ref "S7") (pin "4") (pinfunction "4_4") (pintype "bidirectional"))
    )
    (net (code "23") (name "Net-(F1-Pad1)") (class "Default")
      (node (ref "F1") (pin "1") (pinfunction "1_1") (pintype "bidirectional"))
      (node (ref "J4") (pin "VBUS") (pinfunction "VBUS_VBUS") (pintype "bidirectional"))
    )
    (net (code "24") (name "Net-(J3-Pad4)") (class "Default")
      (node (ref "J3") (pin "4") (pinfunction "4_4") (pintype "passive"))
      (node (ref "R30") (pin "1") (pinfunction "1_1") (pintype "passive"))
      (node (ref "R31") (pin "2") (pinfunction "2_2") (pintype "passive"))
    )
    (net (code "25") (name "Net-(J3-Pad5)") (class "Default")
      (node (ref "J3") (pin "5") (pinfunction "5_5") (pintype "passive"))
      (node (ref "R25") (pin "2") (pinfunction "2_2") (pintype "passive"))
      (node (ref "R26") (pin "1") (pinfunction "1_1") (pintype "passive"))
    )
    (net (code "26") (name "Net-(LED1-K)") (class "Default")
      (node (ref "LED1") (pin "1") (pinfunction "K_1") (pintype "bidirectional"))
      (node (ref "R19") (pin "2") (pinfunction "2_2") (pintype "passive"))
    )
    (net (code "27") (name "Net-(LED2-K)") (class "Default")
      (node (ref "LED2") (pin "1") (pinfunction "K_1") (pintype "bidirectional"))
      (node (ref "R20") (pin "2") (pinfunction "2_2") (pintype "passive"))
    )
    (net (code "28") (name "Net-(LED3-K)") (class "Default")
      (node (ref "LED3") (pin "1") (pinfunction "K_1") (pintype "bidirectional"))
      (node (ref "R24") (pin "2") (pinfunction "2_2") (pintype "passive"))
    )
    (net (code "29") (name "Net-(LS1-PadP)") (class "Default")
      (node (ref "LS1") (pin "P") (pinfunction "P_P") (pintype "passive"))
      (node (ref "R15") (pin "2") (pinfunction "2_2") (pintype "passive"))
    )
    (net (code "30") (name "Net-(Q2-Pad1)") (class "Default")
      (node (ref "Q2") (pin "1") (pinfunction "1_1") (pintype "passive"))
      (node (ref "R27") (pin "1") (pinfunction "1_1") (pintype "passive"))
    )
    (net (code "31") (name "Net-(TH1-THERMOPILE)") (class "Default")
      (node (ref "R2") (pin "1") (pinfunction "1_1") (pintype "passive"))
      (node (ref "TH1") (pin "2") (pinfunction "THERMOPILE_2") (pintype "passive"))
    )
    (net (code "32") (name "Net-(U1-+IN)") (class "Default")
      (node (ref "C1") (pin "2") (pinfunction "2_2") (pintype "passive"))
      (node (ref "C2") (pin "1") (pinfunction "1_1") (pintype "passive"))
      (node (ref "R2") (pin "2") (pinfunction "2_2") (pintype "passive"))
      (node (ref "U1") (pin "3") (pinfunction "+IN_3") (pintype "input"))
    )
    (net (code "33") (name "Net-(U1--IN)") (class "Default")
      (node (ref "C2") (pin "2") (pinfunction "2_2") (pintype "passive"))
      (node (ref "C3") (pin "1") (pinfunction "1_1") (pintype "passive"))
      (node (ref "R3") (pin "2") (pinfunction "2_2") (pintype "passive"))
      (node (ref "U1") (pin "2") (pinfunction "-IN_2") (pintype "input"))
    )
    (net (code "34") (name "Net-(U1-OUTPUT)") (class "Default")
      (node (ref "R5") (pin "1") (pinfunction "1_1") (pintype "passive"))
      (node (ref "TP5") (pin "TP") (pinfunction "TP_TP") (pintype "input"))
      (node (ref "U1") (pin "6") (pinfunction "OUTPUT_6") (pintype "output"))
    )
    (net (code "35") (name "Net-(U1-RG1)") (class "Default")
      (node (ref "R4") (pin "2") (pinfunction "2_2") (pintype "passive"))
      (node (ref "U1") (pin "1") (pinfunction "RG1_1") (pintype "bidirectional"))
    )
    (net (code "36") (name "Net-(U1-RG2)") (class "Default")
      (node (ref "R4") (pin "1") (pinfunction "1_1") (pintype "passive"))
      (node (ref "U1") (pin "8") (pinfunction "RG2_8") (pintype "bidirectional"))
    )
    (net (code "37") (name "Net-(U2-+INA)") (class "Default")
      (node (ref "C6") (pin "1") (pinfunction "1_1") (pintype "passive"))
      (node (ref "R6") (pin "2") (pinfunction "2_2") (pintype "passive"))
      (node (ref "U2") (pin "3") (pinfunction "+INA_3") (pintype "input"))
    )
    (net (code "38") (name "Net-(U2-+INB)") (class "Default")
      (node (ref "R7") (pin "2") (pinfunction "2_2") (pintype "passive"))
      (node (ref "R8") (pin "1") (pinfunction "1_1") (pintype "passive"))
      (node (ref "U2") (pin "5") (pinfunction "+INB_5") (pintype "input"))
    )
    (net (code "39") (name "Net-(U3--IN)") (class "Default")
      (node (ref "R11") (pin "2") (pinfunction "2_2") (pintype "passive"))
      (node (ref "R12") (pin "1") (pinfunction "1_1") (pintype "passive"))
      (node (ref "R29") (pin "2") (pinfunction "2_2") (pintype "passive"))
      (node (ref "U3") (pin "4") (pinfunction "-IN_4") (pintype "bidirectional"))
    )
    (net (code "40") (name "Net-(U3-OUT)") (class "Default")
      (node (ref "Q1") (pin "1") (pinfunction "1_1") (pintype "passive"))
      (node (ref "U3") (pin "1") (pinfunction "OUT_1") (pintype "bidirectional"))
    )
    (net (code "41") (name "Net-(U4-SW)") (class "Default")
      (node (ref "C8") (pin "2") (pinfunction "2_2") (pintype "passive"))
      (node (ref "L1") (pin "1") (pinfunction "1_1") (pintype "bidirectional"))
      (node (ref "U4") (pin "2") (pinfunction "SW_2") (pintype "bidirectional"))
    )
    (net (code "42") (name "Net-(U4-VBST)") (class "Default")
      (node (ref "C8") (pin "1") (pinfunction "1_1") (pintype "passive"))
      (node (ref "U4") (pin "6") (pinfunction "VBST_6") (pintype "bidirectional"))
    )
    (net (code "43") (name "Net-(U4-VFB)") (class "Default")
      (node (ref "R10") (pin "2") (pinfunction "2_2") (pintype "passive"))
      (node (ref "R9") (pin "1") (pinfunction "1_1") (pintype "passive"))
      (node (ref "U4") (pin "4") (pinfunction "VFB_4") (pintype "bidirectional"))
    )
    (net (code "44") (name "Net-(U5-AREF)") (class "Default")
      (node (ref "R13") (pin "2") (pinfunction "2_2") (pintype "passive"))
      (node (ref "U5") (pin "20") (pinfunction "AREF_20") (pintype "passive"))
    )
    (net (code "45") (name "Net-(U5-AVCC)") (class "Default")
      (node (ref "C10") (pin "1") (pinfunction "1_1") (pintype "passive"))
      (node (ref "L2") (pin "2") (pinfunction "2_2") (pintype "passive"))
      (node (ref "U5") (pin "18") (pinfunction "AVCC_18") (pintype "power_in"))
    )
    (net (code "46") (name "Net-(U5-PB3(MOSI{slash}OC2))") (class "Default")
      (node (ref "J2") (pin "5") (pinfunction "5_5") (pintype "bidirectional"))
      (node (ref "U5") (pin "15") (pinfunction "PB3(MOSI/OC2)_15") (pintype "bidirectional"))
    )
    (net (code "47") (name "Net-(U5-PB4(MISO))") (class "Default")
      (node (ref "J2") (pin "3") (pinfunction "3_3") (pintype "bidirectional"))
      (node (ref "U5") (pin "16") (pinfunction "PB4(MISO)_16") (pintype "bidirectional"))
    )
    (net (code "48") (name "Net-(U5-PB5(SCK))") (class "Default")
      (node (ref "J2") (pin "1") (pinfunction "1_1") (pintype "bidirectional"))
      (node (ref "U5") (pin "17") (pinfunction "PB5(SCK)_17") (pintype "bidirectional"))
    )
    (net (code "49") (name "Net-(U5-PB6(XTAL1{slash}TOSC1))") (class "Default")
      (node (ref "C11") (pin "2") (pinfunction "2_2") (pintype "passive"))
      (node (ref "U5") (pin "7") (pinfunction "PB6(XTAL1/TOSC1)_7") (pintype "bidirectional"))
      (node (ref "Y1") (pin "2") (pinfunction "2_2") (pintype "passive"))
    )
    (net (code "50") (name "Net-(U5-PB7(XTAL2{slash}TOSC2))") (class "Default")
      (node (ref "C12") (pin "2") (pinfunction "2_2") (pintype "passive"))
      (node (ref "U5") (pin "8") (pinfunction "PB7(XTAL2/TOSC2)_8") (pintype "bidirectional"))
      (node (ref "Y1") (pin "1") (pinfunction "1_1") (pintype "passive"))
    )
    (net (code "51") (name "Net-(U5-PC4(ADC4{slash}SDA))") (class "Default")
      (node (ref "J1") (pin "4") (pinfunction "4_4") (pintype "passive"))
      (node (ref "U5") (pin "27") (pinfunction "PC4(ADC4/SDA)_27") (pintype "bidirectional"))
    )
    (net (code "52") (name "Net-(U5-PC5(ADC5{slash}SCL))") (class "Default")
      (node (ref "J1") (pin "3") (pinfunction "3_3") (pintype "passive"))
      (node (ref "U5") (pin "28") (pinfunction "PC5(ADC5/SCL)_28") (pintype "bidirectional"))
    )
    (net (code "53") (name "Net-(U5-PD0(RXD))") (class "Default")
      (node (ref "R22") (pin "1") (pinfunction "1_1") (pintype "passive"))
      (node (ref "U5") (pin "30") (pinfunction "PD0(RXD)_30") (pintype "bidirectional"))
    )
    (net (code "54") (name "Net-(U5-PD1(TXD))") (class "Default")
      (node (ref "R21") (pin "1") (pinfunction "1_1") (pintype "passive"))
      (node (ref "U5") (pin "31") (pinfunction "PD1(TXD)_31") (pintype "bidirectional"))
    )
    (net (code "55") (name "Net-(U5-PD5(T1))") (class "Default")
      (node (ref "R15") (pin "1") (pinfunction "1_1") (pintype "passive"))
      (node (ref "U5") (pin "9") (pinfunction "PD5(T1)_9") (pintype "bidirectional"))
    )
    (net (code "56") (name "Net-(U6-3V3OUT)") (class "Default")
      (node (ref "C17") (pin "1") (pinfunction "1_1") (pintype "passive"))
      (node (ref "U6") (pin "17") (pinfunction "3V3OUT_17") (pintype "bidirectional"))
    )
    (net (code "57") (name "Net-(U6-CBUS0)") (class "Default")
      (node (ref "R19") (pin "1") (pinfunction "1_1") (pintype "passive"))
      (node (ref "U6") (pin "23") (pinfunction "CBUS0_23") (pintype "bidirectional"))
    )
    (net (code "58") (name "Net-(U6-CBUS1)") (class "Default")
      (node (ref "R20") (pin "1") (pinfunction "1_1") (pintype "passive"))
      (node (ref "U6") (pin "22") (pinfunction "CBUS1_22") (pintype "bidirectional"))
    )
    (net (code "59") (name "Net-(U6-DTR)") (class "Default")
      (node (ref "C18") (pin "1") (pinfunction "1_1") (pintype "passive"))
      (node (ref "U6") (pin "2") (pinfunction "DTR_2") (pintype "bidirectional"))
    )
    (net (code "60") (name "Net-(U6-USBDM)") (class "Default")
      (node (ref "J4") (pin "D-") (pinfunction "D-_D-") (pintype "bidirectional"))
      (node (ref "U6") (pin "16") (pinfunction "USBDM_16") (pintype "bidirectional"))
    )
    (net (code "61") (name "Net-(U6-USBDP)") (class "Default")
      (node (ref "J4") (pin "D+") (pinfunction "D+_D+") (pintype "bidirectional"))
      (node (ref "U6") (pin "15") (pinfunction "USBDP_15") (pintype "bidirectional"))
    )
    (net (code "62") (name "VCC") (class "Default")
      (node (ref "C13") (pin "1") (pinfunction "1_1") (pintype "passive"))
      (node (ref "C14") (pin "1") (pinfunction "1_1") (pintype "passive"))
      (node (ref "C20") (pin "2") (pinfunction "2_2") (pintype "passive"))
      (node (ref "C9") (pin "1") (pinfunction "1_1") (pintype "passive"))
      (node (ref "D1") (pin "1") (pinfunction "K_1") (pintype "bidirectional"))
      (node (ref "D2") (pin "2") (pinfunction "K_2") (pintype "bidirectional"))
      (node (ref "J2") (pin "2") (pinfunction "2_2") (pintype "bidirectional"))
      (node (ref "L1") (pin "2") (pinfunction "2_2") (pintype "bidirectional"))
      (node (ref "L2") (pin "1") (pinfunction "1_1") (pintype "passive"))
      (node (ref "LED1") (pin "2") (pinfunction "A_2") (pintype "bidirectional"))
      (node (ref "LED2") (pin "2") (pinfunction "A_2") (pintype "bidirectional"))
      (node (ref "Q3") (pin "3") (pinfunction "S_3") (pintype "bidirectional"))
      (node (ref "R14") (pin "2") (pinfunction "2_2") (pintype "passive"))
      (node (ref "R23") (pin "1") (pinfunction "1_1") (pintype "passive"))
      (node (ref "R28") (pin "2") (pinfunction "2_2") (pintype "passive"))
      (node (ref "R9") (pin "2") (pinfunction "2_2") (pintype "passive"))
      (node (ref "S2") (pin "3") (pinfunction "3_3") (pintype "bidirectional"))
      (node (ref "S2") (pin "4") (pinfunction "4_4") (pintype "bidirectional"))
      (node (ref "S3") (pin "3") (pinfunction "3_3") (pintype "bidirectional"))
      (node (ref "S3") (pin "4") (pinfunction "4_4") (pintype "bidirectional"))
      (node (ref "S4") (pin "3") (pinfunction "3_3") (pintype "bidirectional"))
      (node (ref "S4") (pin "4") (pinfunction "4_4") (pintype "bidirectional"))
      (node (ref "TP2") (pin "TP") (pinfunction "TP_TP") (pintype "input"))
      (node (ref "U5") (pin "4") (pinfunction "VCC_4") (pintype "power_in"))
      (node (ref "U5") (pin "6") (pinfunction "VCC_6") (pintype "power_in"))
      (node (ref "U6") (pin "20") (pinfunction "VCC_20") (pintype "bidirectional"))
      (node (ref "U6") (pin "4") (pinfunction "VCCIO_4") (pintype "bidirectional"))
    )
    (net (code "63") (name "VTH") (class "Default")
      (node (ref "C5") (pin "2") (pinfunction "2_2") (pintype "passive"))
      (node (ref "TP7") (pin "TP") (pinfunction "TP_TP") (pintype "input"))
      (node (ref "U2") (pin "1") (pinfunction "OUTA_1") (pintype "output"))
      (node (ref "U2") (pin "2") (pinfunction "-INA_2") (pintype "input"))
      (node (ref "U5") (pin "23") (pinfunction "PC0(ADC0)_23") (pintype "bidirectional"))
    )
    (net (code "64") (name "unconnected-(J3-Pad1)") (class "Default")
      (node (ref "J3") (pin "1") (pinfunction "1_1") (pintype "passive"))
    )
    (net (code "65") (name "unconnected-(J3-Pad6)") (class "Default")
      (node (ref "J3") (pin "6") (pinfunction "6_6") (pintype "passive"))
    )
    (net (code "66") (name "unconnected-(J4-PadID)") (class "Default")
      (node (ref "J4") (pin "ID") (pinfunction "ID_ID") (pintype "bidirectional"))
    )
    (net (code "67") (name "unconnected-(S1-Pad1)") (class "Default")
      (node (ref "S1") (pin "1") (pinfunction "1_1") (pintype "passive"))
    )
    (net (code "68") (name "unconnected-(U5-ADC6-Pad19)") (class "Default")
      (node (ref "U5") (pin "19") (pinfunction "ADC6_19") (pintype "bidirectional"))
    )
    (net (code "69") (name "unconnected-(U5-ADC7-Pad22)") (class "Default")
      (node (ref "U5") (pin "22") (pinfunction "ADC7_22") (pintype "bidirectional"))
    )
    (net (code "70") (name "unconnected-(U5-PC2(ADC2)-Pad25)") (class "Default")
      (node (ref "U5") (pin "25") (pinfunction "PC2(ADC2)_25") (pintype "bidirectional"))
    )
    (net (code "71") (name "unconnected-(U5-PC3(ADC3)-Pad26)") (class "Default")
      (node (ref "U5") (pin "26") (pinfunction "PC3(ADC3)_26") (pintype "bidirectional"))
    )
    (net (code "72") (name "unconnected-(U6-CBUS2-Pad13)") (class "Default")
      (node (ref "U6") (pin "13") (pinfunction "CBUS2_13") (pintype "bidirectional"))
    )
    (net (code "73") (name "unconnected-(U6-CBUS3-Pad14)") (class "Default")
      (node (ref "U6") (pin "14") (pinfunction "CBUS3_14") (pintype "bidirectional"))
    )
    (net (code "74") (name "unconnected-(U6-CBUS4-Pad12)") (class "Default")
      (node (ref "U6") (pin "12") (pinfunction "CBUS4_12") (pintype "bidirectional"))
    )
    (net (code "75") (name "unconnected-(U6-CTS-Pad11)") (class "Default")
      (node (ref "U6") (pin "11") (pinfunction "CTS_11") (pintype "bidirectional"))
    )
    (net (code "76") (name "unconnected-(U6-DCD-Pad10)") (class "Default")
      (node (ref "U6") (pin "10") (pinfunction "DCD_10") (pintype "bidirectional"))
    )
    (net (code "77") (name "unconnected-(U6-DSR-Pad9)") (class "Default")
      (node (ref "U6") (pin "9") (pinfunction "DSR_9") (pintype "bidirectional"))
    )
    (net (code "78") (name "unconnected-(U6-NC8-Pad8)") (class "Default")
      (node (ref "U6") (pin "8") (pinfunction "NC8_8") (pintype "bidirectional"))
    )
    (net (code "79") (name "unconnected-(U6-NC24-Pad24)") (class "Default")
      (node (ref "U6") (pin "24") (pinfunction "NC24_24") (pintype "bidirectional"))
    )
    (net (code "80") (name "unconnected-(U6-OSCI-Pad27)") (class "Default")
      (node (ref "U6") (pin "27") (pinfunction "OSCI_27") (pintype "bidirectional"))
    )
    (net (code "81") (name "unconnected-(U6-OSCO-Pad28)") (class "Default")
      (node (ref "U6") (pin "28") (pinfunction "OSCO_28") (pintype "bidirectional"))
    )
    (net (code "82") (name "unconnected-(U6-RESET-Pad19)") (class "Default")
      (node (ref "U6") (pin "19") (pinfunction "RESET_19") (pintype "bidirectional"))
    )
    (net (code "83") (name "unconnected-(U6-RI-Pad6)") (class "Default")
      (node (ref "U6") (pin "6") (pinfunction "RI_6") (pintype "bidirectional"))
    )
    (net (code "84") (name "unconnected-(U6-RTS-Pad3)") (class "Default")
      (node (ref "U6") (pin "3") (pinfunction "RTS_3") (pintype "bidirectional"))
    )
  )
)
